# Boost_convertor.net
KiCad netlist of a schematic drawn in Altium Designer
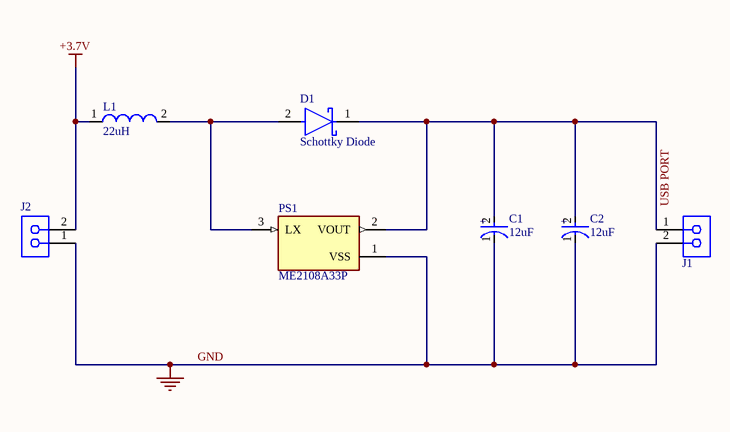
[diagram p0: Boost convertor.SchDoc]

(export (version "E")
  (design (tool "Eeschema 10.0.6"))
  (components
    (comp (ref "C1")
      (value "12uF")
      (footprint "FP-RAD-TH-D_5_0_5-L_7_1-F-MFG")
      (description "Aluminum Electrolytic Capacitors (Radial Lead Type) AEC-Q200 Qualified 12uF ±20% 35V")
      (fields (field (name "VOLTAGE") "35V") (field (name "TOLERANCE") "20%"))
      (libsource (lib "Altium Content Vault") (part "a00bbbee19879c290e62620ae7e47b1"))
    )
    (comp (ref "C2")
      (value "12uF")
      (footprint "FP-RAD-TH-D_5_0_5-L_7_1-F-MFG")
      (description "Aluminum Electrolytic Capacitors (Radial Lead Type) AEC-Q200 Qualified 12uF ±20% 35V")
      (fields (field (name "VOLTAGE") "35V") (field (name "TOLERANCE") "20%"))
      (libsource (lib "Altium Content Vault") (part "a00bbbee19879c290e62620ae7e47b1"))
    )
    (comp (ref "D1")
      (value "Schottky Diode")
      (footprint "FP-DO-41-MFG")
      (description "DIODE SCHOTTKY 20V 1A DO41")
      (libsource (lib "Altium Content Vault") (part "1d6ec82d83fb6aee721767c19dac4b9"))
    )
    (comp (ref "J1")
      (value "SSW-102-02-T-S")
      (footprint "SMTC-SSW-102-02-X-S")
      (description "SQ Post Socket, Through-hole, Vertical, -55 to 105 degC, 2.54 mm Pitch, 2-Pin, Female, RoHS")
      (fields (field (name "MANUFACTURER") "Samtec"))
      (libsource (lib "Altium Content Vault") (part "SMTC-SSW-102-02-X-S-X"))
    )
    (comp (ref "J2")
      (value "SSW-102-02-T-S")
      (footprint "SMTC-SSW-102-02-X-S")
      (description "SQ Post Socket, Through-hole, Vertical, -55 to 105 degC, 2.54 mm Pitch, 2-Pin, Female, RoHS")
      (fields (field (name "MANUFACTURER") "Samtec"))
      (libsource (lib "Altium Content Vault") (part "SMTC-SSW-102-02-X-S-X"))
    )
    (comp (ref "L1")
      (value "22uH")
      (footprint "WE-TIS 1111")
      (description "Shielded Radial Leaded Wire Wound Inductor WE-TIS, L=22.0 µH")
      (fields (field (name "PARTNUMBER") "7447471220") (field (name "MANUFACTURER") "Wuerth Elektronik"))
      (libsource (lib "Altium Content Vault") (part "PAS-IND-INDUCTOR-2"))
    )
    (comp (ref "PS1")
      (value "ME2108A33P")
      (footprint "CONV_ME2108A33P")
      (description "PFM Step-up Step-up Step-up Step-up DC/DC Converter")
      (fields (field (name "MF") "Nanjing Micro One Electronics"))
      (libsource (lib "ME2108A33P") (part "ME2108A33P"))
    )
  )
  (nets
    (net (code "1") (name "+3.7V") (class "Default")
      (node (ref "J2") (pin "2") (pinfunction "2_2") (pintype "passive"))
      (node (ref "L1") (pin "1") (pinfunction "1_1") (pintype "passive"))
    )
    (net (code "2") (name "/USB PORT") (class "Default")
      (node (ref "C1") (pin "2") (pinfunction "A_2") (pintype "passive"))
      (node (ref "C2") (pin "2") (pinfunction "A_2") (pintype "passive"))
      (node (ref "D1") (pin "1") (pinfunction "C_1") (pintype "passive"))
      (node (ref "J1") (pin "1") (pinfunction "1_1") (pintype "passive"))
      (node (ref "PS1") (pin "2") (pinfunction "VOUT_2") (pintype "output"))
    )
    (net (code "3") (name "GND") (class "Default")
      (node (ref "C1") (pin "1") (pinfunction "C_1") (pintype "passive"))
      (node (ref "C2") (pin "1") (pinfunction "C_1") (pintype "passive"))
      (node (ref "J1") (pin "2") (pinfunction "2_2") (pintype "passive"))
      (node (ref "J2") (pin "1") (pinfunction "1_1") (pintype "passive"))
      (node (ref "PS1") (pin "1") (pinfunction "VSS_1") (pintype "power_in"))
    )
    (net (code "4") (name "Net-(D1-A)") (class "Default")
      (node (ref "D1") (pin "2") (pinfunction "A_2") (pintype "passive"))
      (node (ref "L1") (pin "2") (pinfunction "2_2") (pintype "passive"))
      (node (ref "PS1") (pin "3") (pinfunction "LX_3") (pintype "input"))
    )
  )
)
